# JC1001-1.net
KiCad netlist of a schematic drawn in Altium Designer
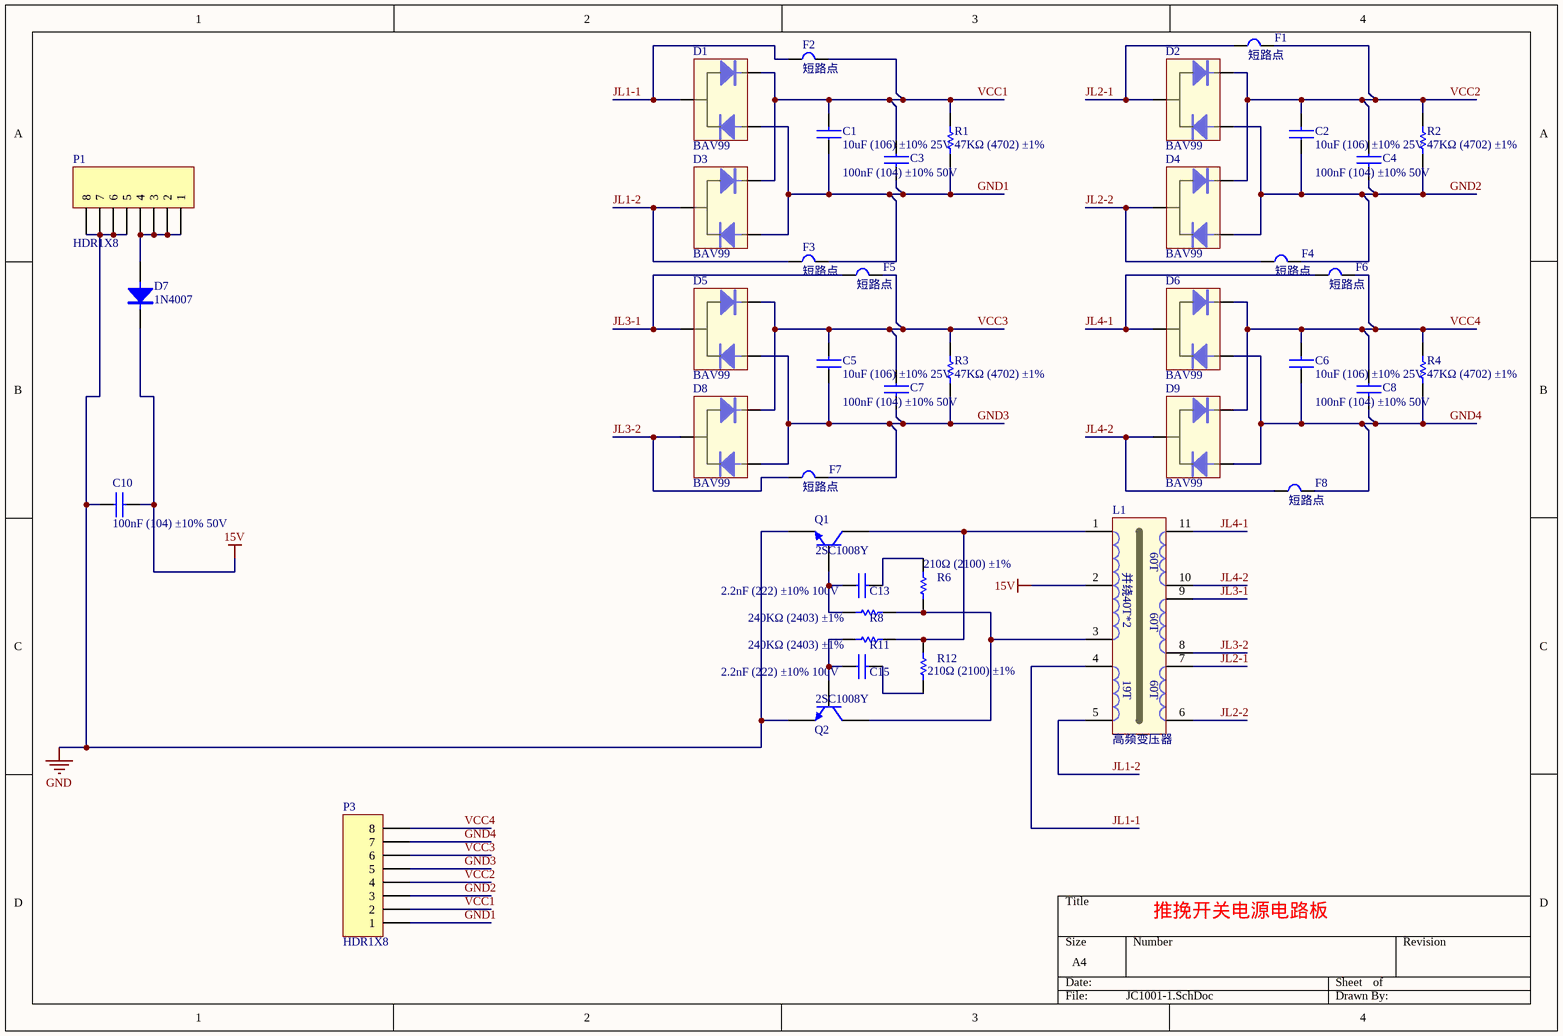
[diagram p0: JC1001-1.SchDoc]

(export (version "E")
  (design (tool "Eeschema 10.0.6"))
  (components
    (comp (ref "C1")
      (value "10uF (106) ±10% 25V")
      (footprint "C0805")
      (description "0805X106K250NT")
      (libsource (lib "JCSchLib") (part "C贴片电容(C0805) 10uF (106) ±10% 25V"))
    )
    (comp (ref "C2")
      (value "10uF (106) ±10% 25V")
      (footprint "C0805")
      (description "0805X106K250NT")
      (libsource (lib "JCSchLib") (part "C贴片电容(C0805) 10uF (106) ±10% 25V"))
    )
    (comp (ref "C3")
      (value "100nF (104) ±10% 50V")
      (footprint "C0805")
      (description "CL21B104KBCNNNC")
      (libsource (lib "JCSchLib") (part "C贴片电容(C0805) 100nF (104) ±10% 50V"))
    )
    (comp (ref "C4")
      (value "100nF (104) ±10% 50V")
      (footprint "C0805")
      (description "CL21B104KBCNNNC")
      (libsource (lib "JCSchLib") (part "C贴片电容(C0805) 100nF (104) ±10% 50V"))
    )
    (comp (ref "C5")
      (value "10uF (106) ±10% 25V")
      (footprint "C0805")
      (description "0805X106K250NT")
      (libsource (lib "JCSchLib") (part "C贴片电容(C0805) 10uF (106) ±10% 25V"))
    )
    (comp (ref "C6")
      (value "10uF (106) ±10% 25V")
      (footprint "C0805")
      (description "0805X106K250NT")
      (libsource (lib "JCSchLib") (part "C贴片电容(C0805) 10uF (106) ±10% 25V"))
    )
    (comp (ref "C7")
      (value "100nF (104) ±10% 50V")
      (footprint "C0805")
      (description "CL21B104KBCNNNC")
      (libsource (lib "JCSchLib") (part "C贴片电容(C0805) 100nF (104) ±10% 50V"))
    )
    (comp (ref "C8")
      (value "100nF (104) ±10% 50V")
      (footprint "C0805")
      (description "CL21B104KBCNNNC")
      (libsource (lib "JCSchLib") (part "C贴片电容(C0805) 100nF (104) ±10% 50V"))
    )
    (comp (ref "C10")
      (value "100nF (104) ±10% 50V")
      (footprint "C0805")
      (description "CL21B104KBCNNNC")
      (libsource (lib "JCSchLib") (part "C贴片电容(C0805) 100nF (104) ±10% 50V"))
    )
    (comp (ref "C13")
      (value "2.2nF (222) ±10% 100V")
      (footprint "C0805")
      (description "CL21B222KCANNNC")
      (libsource (lib "JCSchLib") (part "C贴片电容(C0805) 2.2nF (222) ±10% 100V"))
    )
    (comp (ref "C15")
      (value "2.2nF (222) ±10% 100V")
      (footprint "C0805")
      (description "CL21B222KCANNNC")
      (libsource (lib "JCSchLib") (part "C贴片电容(C0805) 2.2nF (222) ±10% 100V"))
    )
    (comp (ref "D1")
      (value "BAV99")
      (footprint "SOT-23-3L")
      (libsource (lib "JCSchLib") (part "D贴片开关二极管(SOT-23-3L) BAV99"))
    )
    (comp (ref "D2")
      (value "BAV99")
      (footprint "SOT-23-3L")
      (libsource (lib "JCSchLib") (part "D贴片开关二极管(SOT-23-3L) BAV99"))
    )
    (comp (ref "D3")
      (value "BAV99")
      (footprint "SOT-23-3L")
      (libsource (lib "JCSchLib") (part "D贴片开关二极管(SOT-23-3L) BAV99"))
    )
    (comp (ref "D4")
      (value "BAV99")
      (footprint "SOT-23-3L")
      (libsource (lib "JCSchLib") (part "D贴片开关二极管(SOT-23-3L) BAV99"))
    )
    (comp (ref "D5")
      (value "BAV99")
      (footprint "SOT-23-3L")
      (libsource (lib "JCSchLib") (part "D贴片开关二极管(SOT-23-3L) BAV99"))
    )
    (comp (ref "D6")
      (value "BAV99")
      (footprint "SOT-23-3L")
      (libsource (lib "JCSchLib") (part "D贴片开关二极管(SOT-23-3L) BAV99"))
    )
    (comp (ref "D7")
      (value "1N4007")
      (footprint "SMA")
      (description "M7")
      (libsource (lib "JCSchLib") (part "D贴片整流管(SMA) 1N4007"))
    )
    (comp (ref "D8")
      (value "BAV99")
      (footprint "SOT-23-3L")
      (libsource (lib "JCSchLib") (part "D贴片开关二极管(SOT-23-3L) BAV99"))
    )
    (comp (ref "D9")
      (value "BAV99")
      (footprint "SOT-23-3L")
      (libsource (lib "JCSchLib") (part "D贴片开关二极管(SOT-23-3L) BAV99"))
    )
    (comp (ref "F1")
      (value "短路点")
      (footprint "SCP-2")
      (description "半圆短路点")
      (libsource (lib "JCSchLib") (part "F贴片跳线开关(SCP-2) 半圆短路点"))
    )
    (comp (ref "F2")
      (value "短路点")
      (footprint "SCP-2")
      (description "半圆短路点")
      (libsource (lib "JCSchLib") (part "F贴片跳线开关(SCP-2) 半圆短路点"))
    )
    (comp (ref "F3")
      (value "短路点")
      (footprint "SCP-2")
      (description "半圆短路点")
      (libsource (lib "JCSchLib") (part "F贴片跳线开关(SCP-2) 半圆短路点"))
    )
    (comp (ref "F4")
      (value "短路点")
      (footprint "SCP-2")
      (description "半圆短路点")
      (libsource (lib "JCSchLib") (part "F贴片跳线开关(SCP-2) 半圆短路点"))
    )
    (comp (ref "F5")
      (value "短路点")
      (footprint "SCP-2")
      (description "半圆短路点")
      (libsource (lib "JCSchLib") (part "F贴片跳线开关(SCP-2) 半圆短路点"))
    )
    (comp (ref "F6")
      (value "短路点")
      (footprint "SCP-2")
      (description "半圆短路点")
      (libsource (lib "JCSchLib") (part "F贴片跳线开关(SCP-2) 半圆短路点"))
    )
    (comp (ref "F7")
      (value "短路点")
      (footprint "SCP-2")
      (description "半圆短路点")
      (libsource (lib "JCSchLib") (part "F贴片跳线开关(SCP-2) 半圆短路点"))
    )
    (comp (ref "F8")
      (value "短路点")
      (footprint "SCP-2")
      (description "半圆短路点")
      (libsource (lib "JCSchLib") (part "F贴片跳线开关(SCP-2) 半圆短路点"))
    )
    (comp (ref "L1")
      (value "高频变压器")
      (footprint "EPC13-11")
      (description "EPC13-15-5-20*3")
      (libsource (lib "JCSchLib") (part "L直插变压器(EPC13-11) EPC13-15-5-20*3"))
    )
    (comp (ref "P1")
      (value "HDR1X8")
      (footprint "HDR1X8")
      (libsource (lib "") (part "P标准插针2.54间距(HDR?*?)  HDR1X8_1"))
    )
    (comp (ref "P3")
      (value "HDR1X8")
      (footprint "HDR1X8")
      (libsource (lib "JCSchLib") (part "P标准插针2.54间距(HDR?*?)  HDR1X8"))
    )
    (comp (ref "Q1")
      (value "2SC1008Y")
      (footprint "TO-92-3")
      (libsource (lib "JCSchLib") (part "Q直插三极管(TO-92-3) 2SC1008Y NPN"))
    )
    (comp (ref "Q2")
      (value "2SC1008Y")
      (footprint "TO-92-3")
      (libsource (lib "JCSchLib") (part "Q直插三极管(TO-92-3) 2SC1008Y NPN"))
    )
    (comp (ref "R1")
      (value "47KΩ (4702) ±1%")
      (footprint "R0805")
      (description "0805W8F4702T5E")
      (libsource (lib "JCSchLib") (part "R贴片电阻(R0805) 47KΩ (4702) ±1%"))
    )
    (comp (ref "R2")
      (value "47KΩ (4702) ±1%")
      (footprint "R0805")
      (description "0805W8F4702T5E")
      (libsource (lib "JCSchLib") (part "R贴片电阻(R0805) 47KΩ (4702) ±1%"))
    )
    (comp (ref "R3")
      (value "47KΩ (4702) ±1%")
      (footprint "R0805")
      (description "0805W8F4702T5E")
      (libsource (lib "JCSchLib") (part "R贴片电阻(R0805) 47KΩ (4702) ±1%"))
    )
    (comp (ref "R4")
      (value "47KΩ (4702) ±1%")
      (footprint "R0805")
      (description "0805W8F4702T5E")
      (libsource (lib "JCSchLib") (part "R贴片电阻(R0805) 47KΩ (4702) ±1%"))
    )
    (comp (ref "R6")
      (value "210Ω (2100) ±1%")
      (footprint "R0805")
      (description "0805W8F2100T5E")
      (libsource (lib "JCSchLib") (part "R贴片电阻(R0805) 210Ω (2100) ±1%"))
    )
    (comp (ref "R8")
      (value "240KΩ (2403) ±1%")
      (footprint "R0805")
      (description "0805W8F2403T5E")
      (libsource (lib "JCSchLib") (part "R贴片电阻(R0805) 240KΩ (2403) ±1%"))
    )
    (comp (ref "R11")
      (value "240KΩ (2403) ±1%")
      (footprint "R0805")
      (description "0805W8F2403T5E")
      (libsource (lib "JCSchLib") (part "R贴片电阻(R0805) 240KΩ (2403) ±1%"))
    )
    (comp (ref "R12")
      (value "210Ω (2100) ±1%")
      (footprint "R0805")
      (description "0805W8F2100T5E")
      (libsource (lib "JCSchLib") (part "R贴片电阻(R0805) 210Ω (2100) ±1%"))
    )
  )
  (nets
    (net (code "1") (name "/GND1") (class "Default")
      (node (ref "C1") (pin "1") (pinfunction "1_1") (pintype "passive"))
      (node (ref "C3") (pin "2") (pinfunction "2_2") (pintype "passive"))
      (node (ref "D1") (pin "1") (pinfunction "1_1") (pintype "passive"))
      (node (ref "D3") (pin "1") (pinfunction "1_1") (pintype "passive"))
      (node (ref "F3") (pin "2") (pinfunction "2_2") (pintype "passive"))
      (node (ref "P3") (pin "1") (pinfunction "1_1") (pintype "passive"))
      (node (ref "R1") (pin "1") (pinfunction "1_1") (pintype "passive"))
    )
    (net (code "2") (name "/GND2") (class "Default")
      (node (ref "C2") (pin "1") (pinfunction "1_1") (pintype "passive"))
      (node (ref "C4") (pin "2") (pinfunction "2_2") (pintype "passive"))
      (node (ref "D2") (pin "1") (pinfunction "1_1") (pintype "passive"))
      (node (ref "D4") (pin "1") (pinfunction "1_1") (pintype "passive"))
      (node (ref "F4") (pin "2") (pinfunction "2_2") (pintype "passive"))
      (node (ref "P3") (pin "3") (pinfunction "3_3") (pintype "passive"))
      (node (ref "R2") (pin "1") (pinfunction "1_1") (pintype "passive"))
    )
    (net (code "3") (name "/GND3") (class "Default")
      (node (ref "C5") (pin "1") (pinfunction "1_1") (pintype "passive"))
      (node (ref "C7") (pin "2") (pinfunction "2_2") (pintype "passive"))
      (node (ref "D5") (pin "1") (pinfunction "1_1") (pintype "passive"))
      (node (ref "D8") (pin "1") (pinfunction "1_1") (pintype "passive"))
      (node (ref "F7") (pin "2") (pinfunction "2_2") (pintype "passive"))
      (node (ref "P3") (pin "5") (pinfunction "5_5") (pintype "passive"))
      (node (ref "R3") (pin "1") (pinfunction "1_1") (pintype "passive"))
    )
    (net (code "4") (name "/GND4") (class "Default")
      (node (ref "C6") (pin "1") (pinfunction "1_1") (pintype "passive"))
      (node (ref "C8") (pin "2") (pinfunction "2_2") (pintype "passive"))
      (node (ref "D6") (pin "1") (pinfunction "1_1") (pintype "passive"))
      (node (ref "D9") (pin "1") (pinfunction "1_1") (pintype "passive"))
      (node (ref "F8") (pin "2") (pinfunction "2_2") (pintype "passive"))
      (node (ref "P3") (pin "7") (pinfunction "7_7") (pintype "passive"))
      (node (ref "R4") (pin "1") (pinfunction "1_1") (pintype "passive"))
    )
    (net (code "5") (name "/JL1-1") (class "Default")
      (node (ref "D1") (pin "3") (pinfunction "3_3") (pintype "passive"))
      (node (ref "F2") (pin "1") (pinfunction "1_1") (pintype "passive"))
      (node (ref "L1") (pin "4") (pinfunction "4_4") (pintype "passive"))
    )
    (net (code "6") (name "/JL1-2") (class "Default")
      (node (ref "D3") (pin "3") (pinfunction "3_3") (pintype "passive"))
      (node (ref "F3") (pin "1") (pinfunction "1_1") (pintype "passive"))
      (node (ref "L1") (pin "5") (pinfunction "5_5") (pintype "passive"))
    )
    (net (code "7") (name "/JL2-1") (class "Default")
      (node (ref "D2") (pin "3") (pinfunction "3_3") (pintype "passive"))
      (node (ref "F1") (pin "1") (pinfunction "1_1") (pintype "passive"))
      (node (ref "L1") (pin "7") (pinfunction "7_7") (pintype "passive"))
    )
    (net (code "8") (name "/JL2-2") (class "Default")
      (node (ref "D4") (pin "3") (pinfunction "3_3") (pintype "passive"))
      (node (ref "F4") (pin "1") (pinfunction "1_1") (pintype "passive"))
      (node (ref "L1") (pin "6") (pinfunction "6_6") (pintype "passive"))
    )
    (net (code "9") (name "/JL3-1") (class "Default")
      (node (ref "D5") (pin "3") (pinfunction "3_3") (pintype "passive"))
      (node (ref "F5") (pin "1") (pinfunction "1_1") (pintype "passive"))
      (node (ref "L1") (pin "9") (pinfunction "9_9") (pintype "passive"))
    )
    (net (code "10") (name "/JL3-2") (class "Default")
      (node (ref "D8") (pin "3") (pinfunction "3_3") (pintype "passive"))
      (node (ref "F7") (pin "1") (pinfunction "1_1") (pintype "passive"))
      (node (ref "L1") (pin "8") (pinfunction "8_8") (pintype "passive"))
    )
    (net (code "11") (name "/JL4-1") (class "Default")
      (node (ref "D6") (pin "3") (pinfunction "3_3") (pintype "passive"))
      (node (ref "F6") (pin "1") (pinfunction "1_1") (pintype "passive"))
      (node (ref "L1") (pin "11") (pinfunction "11_11") (pintype "passive"))
    )
    (net (code "12") (name "/JL4-2") (class "Default")
      (node (ref "D9") (pin "3") (pinfunction "3_3") (pintype "passive"))
      (node (ref "F8") (pin "1") (pinfunction "1_1") (pintype "passive"))
      (node (ref "L1") (pin "10") (pinfunction "10_10") (pintype "passive"))
    )
    (net (code "13") (name "/VCC1") (class "Default")
      (node (ref "C1") (pin "2") (pinfunction "2_2") (pintype "passive"))
      (node (ref "C3") (pin "1") (pinfunction "1_1") (pintype "passive"))
      (node (ref "D1") (pin "2") (pinfunction "2_2") (pintype "passive"))
      (node (ref "D3") (pin "2") (pinfunction "2_2") (pintype "passive"))
      (node (ref "F2") (pin "2") (pinfunction "2_2") (pintype "passive"))
      (node (ref "P3") (pin "2") (pinfunction "2_2") (pintype "passive"))
      (node (ref "R1") (pin "2") (pinfunction "2_2") (pintype "passive"))
    )
    (net (code "14") (name "/VCC2") (class "Default")
      (node (ref "C2") (pin "2") (pinfunction "2_2") (pintype "passive"))
      (node (ref "C4") (pin "1") (pinfunction "1_1") (pintype "passive"))
      (node (ref "D2") (pin "2") (pinfunction "2_2") (pintype "passive"))
      (node (ref "D4") (pin "2") (pinfunction "2_2") (pintype "passive"))
      (node (ref "F1") (pin "2") (pinfunction "2_2") (pintype "passive"))
      (node (ref "P3") (pin "4") (pinfunction "4_4") (pintype "passive"))
      (node (ref "R2") (pin "2") (pinfunction "2_2") (pintype "passive"))
    )
    (net (code "15") (name "/VCC3") (class "Default")
      (node (ref "C5") (pin "2") (pinfunction "2_2") (pintype "passive"))
      (node (ref "C7") (pin "1") (pinfunction "1_1") (pintype "passive"))
      (node (ref "D5") (pin "2") (pinfunction "2_2") (pintype "passive"))
      (node (ref "D8") (pin "2") (pinfunction "2_2") (pintype "passive"))
      (node (ref "F5") (pin "2") (pinfunction "2_2") (pintype "passive"))
      (node (ref "P3") (pin "6") (pinfunction "6_6") (pintype "passive"))
      (node (ref "R3") (pin "2") (pinfunction "2_2") (pintype "passive"))
    )
    (net (code "16") (name "/VCC4") (class "Default")
      (node (ref "C6") (pin "2") (pinfunction "2_2") (pintype "passive"))
      (node (ref "C8") (pin "1") (pinfunction "1_1") (pintype "passive"))
      (node (ref "D6") (pin "2") (pinfunction "2_2") (pintype "passive"))
      (node (ref "D9") (pin "2") (pinfunction "2_2") (pintype "passive"))
      (node (ref "F6") (pin "2") (pinfunction "2_2") (pintype "passive"))
      (node (ref "P3") (pin "8") (pinfunction "8_8") (pintype "passive"))
      (node (ref "R4") (pin "2") (pinfunction "2_2") (pintype "passive"))
    )
    (net (code "17") (name "15V") (class "Default")
      (node (ref "C10") (pin "2") (pinfunction "2_2") (pintype "passive"))
      (node (ref "D7") (pin "2") (pinfunction "K_2") (pintype "passive"))
      (node (ref "L1") (pin "2") (pinfunction "2_2") (pintype "passive"))
    )
    (net (code "18") (name "GND") (class "Default")
      (node (ref "C10") (pin "1") (pinfunction "1_1") (pintype "passive"))
      (node (ref "P1") (pin "5") (pinfunction "5_5") (pintype "passive"))
      (node (ref "P1") (pin "6") (pinfunction "6_6") (pintype "passive"))
      (node (ref "P1") (pin "7") (pinfunction "7_7") (pintype "passive"))
      (node (ref "P1") (pin "8") (pinfunction "8_8") (pintype "passive"))
      (node (ref "Q1") (pin "1") (pinfunction "E_1") (pintype "passive"))
      (node (ref "Q2") (pin "1") (pinfunction "E_1") (pintype "passive"))
    )
    (net (code "19") (name "Net-(C13-Pad2)") (class "Default")
      (node (ref "C13") (pin "2") (pinfunction "2_2") (pintype "passive"))
      (node (ref "R6") (pin "2") (pinfunction "2_2") (pintype "passive"))
    )
    (net (code "20") (name "Net-(C15-Pad2)") (class "Default")
      (node (ref "C15") (pin "2") (pinfunction "2_2") (pintype "passive"))
      (node (ref "R12") (pin "1") (pinfunction "1_1") (pintype "passive"))
    )
    (net (code "21") (name "Net-(D7-A)") (class "Default")
      (node (ref "D7") (pin "1") (pinfunction "A_1") (pintype "passive"))
      (node (ref "P1") (pin "1") (pinfunction "1_1") (pintype "passive"))
      (node (ref "P1") (pin "2") (pinfunction "2_2") (pintype "passive"))
      (node (ref "P1") (pin "3") (pinfunction "3_3") (pintype "passive"))
      (node (ref "P1") (pin "4") (pinfunction "4_4") (pintype "passive"))
    )
    (net (code "22") (name "Net-(Q1-B)") (class "Default")
      (node (ref "C13") (pin "1") (pinfunction "1_1") (pintype "passive"))
      (node (ref "Q1") (pin "2") (pinfunction "B_2") (pintype "passive"))
      (node (ref "R8") (pin "2") (pinfunction "2_2") (pintype "passive"))
    )
    (net (code "23") (name "Net-(Q1-C)") (class "Default")
      (node (ref "L1") (pin "1") (pinfunction "1_1") (pintype "passive"))
      (node (ref "Q1") (pin "3") (pinfunction "C_3") (pintype "passive"))
      (node (ref "R11") (pin "1") (pinfunction "1_1") (pintype "passive"))
      (node (ref "R12") (pin "2") (pinfunction "2_2") (pintype "passive"))
    )
    (net (code "24") (name "Net-(Q2-B)") (class "Default")
      (node (ref "C15") (pin "1") (pinfunction "1_1") (pintype "passive"))
      (node (ref "Q2") (pin "2") (pinfunction "B_2") (pintype "passive"))
      (node (ref "R11") (pin "2") (pinfunction "2_2") (pintype "passive"))
    )
    (net (code "25") (name "Net-(Q2-C)") (class "Default")
      (node (ref "L1") (pin "3") (pinfunction "3_3") (pintype "passive"))
      (node (ref "Q2") (pin "3") (pinfunction "C_3") (pintype "passive"))
      (node (ref "R6") (pin "1") (pinfunction "1_1") (pintype "passive"))
      (node (ref "R8") (pin "1") (pinfunction "1_1") (pintype "passive"))
    )
  )
)
